# Input_Gain.net
KiCad netlist of a schematic drawn in Altium Designer
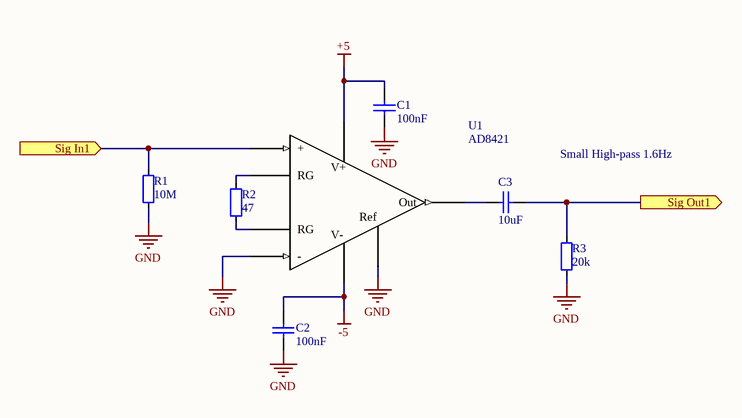
[diagram p0: Input_Gain.SchDoc]

(export (version "E")
  (design (tool "Eeschema 10.0.6"))
  (components
    (comp (ref "C1")
      (value "100nF")
      (footprint "CAPC0603M")
      (description "Ceramic capacitor")
      (fields (field (name "Comment") "Cap"))
      (libsource (lib "KNR_Kurs") (part "Cap"))
    )
    (comp (ref "C2")
      (value "100nF")
      (footprint "CAPC0603M")
      (description "Ceramic capacitor")
      (fields (field (name "Comment") "Cap"))
      (libsource (lib "KNR_Kurs") (part "Cap"))
    )
    (comp (ref "C3")
      (value "10uF")
      (footprint "CAPC0603M")
      (description "Ceramic capacitor")
      (fields (field (name "Comment") "Cap"))
      (libsource (lib "KNR_Kurs") (part "Cap"))
    )
    (comp (ref "R1")
      (value "10M")
      (footprint "RESC0603")
      (description "Resistior")
      (libsource (lib "KNR_Kurs") (part "RES"))
    )
    (comp (ref "R2")
      (value "47")
      (footprint "RESC0603")
      (description "Resistior")
      (libsource (lib "KNR_Kurs") (part "RES"))
    )
    (comp (ref "R3")
      (value "20k")
      (footprint "RESC0603")
      (description "Resistior")
      (libsource (lib "KNR_Kurs") (part "RES"))
    )
    (comp (ref "U1")
      (value "AD8421")
      (footprint "SOIC127P600X175-8N")
      (description "10MHz    +-2.5-18V  Instrumentation Amplifier")
      (libsource (lib "Sonar_OKOŃ") (part "AD8421"))
    )
  )
  (nets
    (net (code "1") (name "+5") (class "Default")
      (node (ref "C1") (pin "2") (pinfunction "2_2") (pintype "passive"))
      (node (ref "U1") (pin "8") (pinfunction "V+_8") (pintype "power_in"))
    )
    (net (code "2") (name "-5") (class "Default")
      (node (ref "C2") (pin "1") (pinfunction "1_1") (pintype "passive"))
      (node (ref "U1") (pin "5") (pinfunction "V-_5") (pintype "power_in"))
    )
    (net (code "3") (name "/Sig In1") (class "Default")
      (node (ref "R1") (pin "2") (pinfunction "2_2") (pintype "passive"))
      (node (ref "U1") (pin "4") (pinfunction "+_4") (pintype "input"))
    )
    (net (code "4") (name "/Sig Out1") (class "Default")
      (node (ref "C3") (pin "2") (pinfunction "2_2") (pintype "passive"))
      (node (ref "R3") (pin "2") (pinfunction "2_2") (pintype "passive"))
    )
    (net (code "5") (name "GND") (class "Default")
      (node (ref "C1") (pin "1") (pinfunction "1_1") (pintype "passive"))
      (node (ref "C2") (pin "2") (pinfunction "2_2") (pintype "passive"))
      (node (ref "R1") (pin "1") (pinfunction "1_1") (pintype "passive"))
      (node (ref "R3") (pin "1") (pinfunction "1_1") (pintype "passive"))
      (node (ref "U1") (pin "1") (pinfunction "-_1") (pintype "input"))
      (node (ref "U1") (pin "6") (pinfunction "Ref_6") (pintype "passive"))
    )
    (net (code "6") (name "Net-(R2-Pad1)") (class "Default")
      (node (ref "R2") (pin "1") (pinfunction "1_1") (pintype "passive"))
      (node (ref "U1") (pin "3") (pinfunction "RG_3") (pintype "passive"))
    )
    (net (code "7") (name "Net-(R2-Pad2)") (class "Default")
      (node (ref "R2") (pin "2") (pinfunction "2_2") (pintype "passive"))
      (node (ref "U1") (pin "2") (pinfunction "RG_2") (pintype "passive"))
    )
    (net (code "8") (name "Net-(U1-Out)") (class "Default")
      (node (ref "C3") (pin "1") (pinfunction "1_1") (pintype "passive"))
      (node (ref "U1") (pin "7") (pinfunction "Out_7") (pintype "output"))
    )
  )
)
